# USB_HUB_3_0.net
KiCad netlist of a schematic drawn in Altium Designer
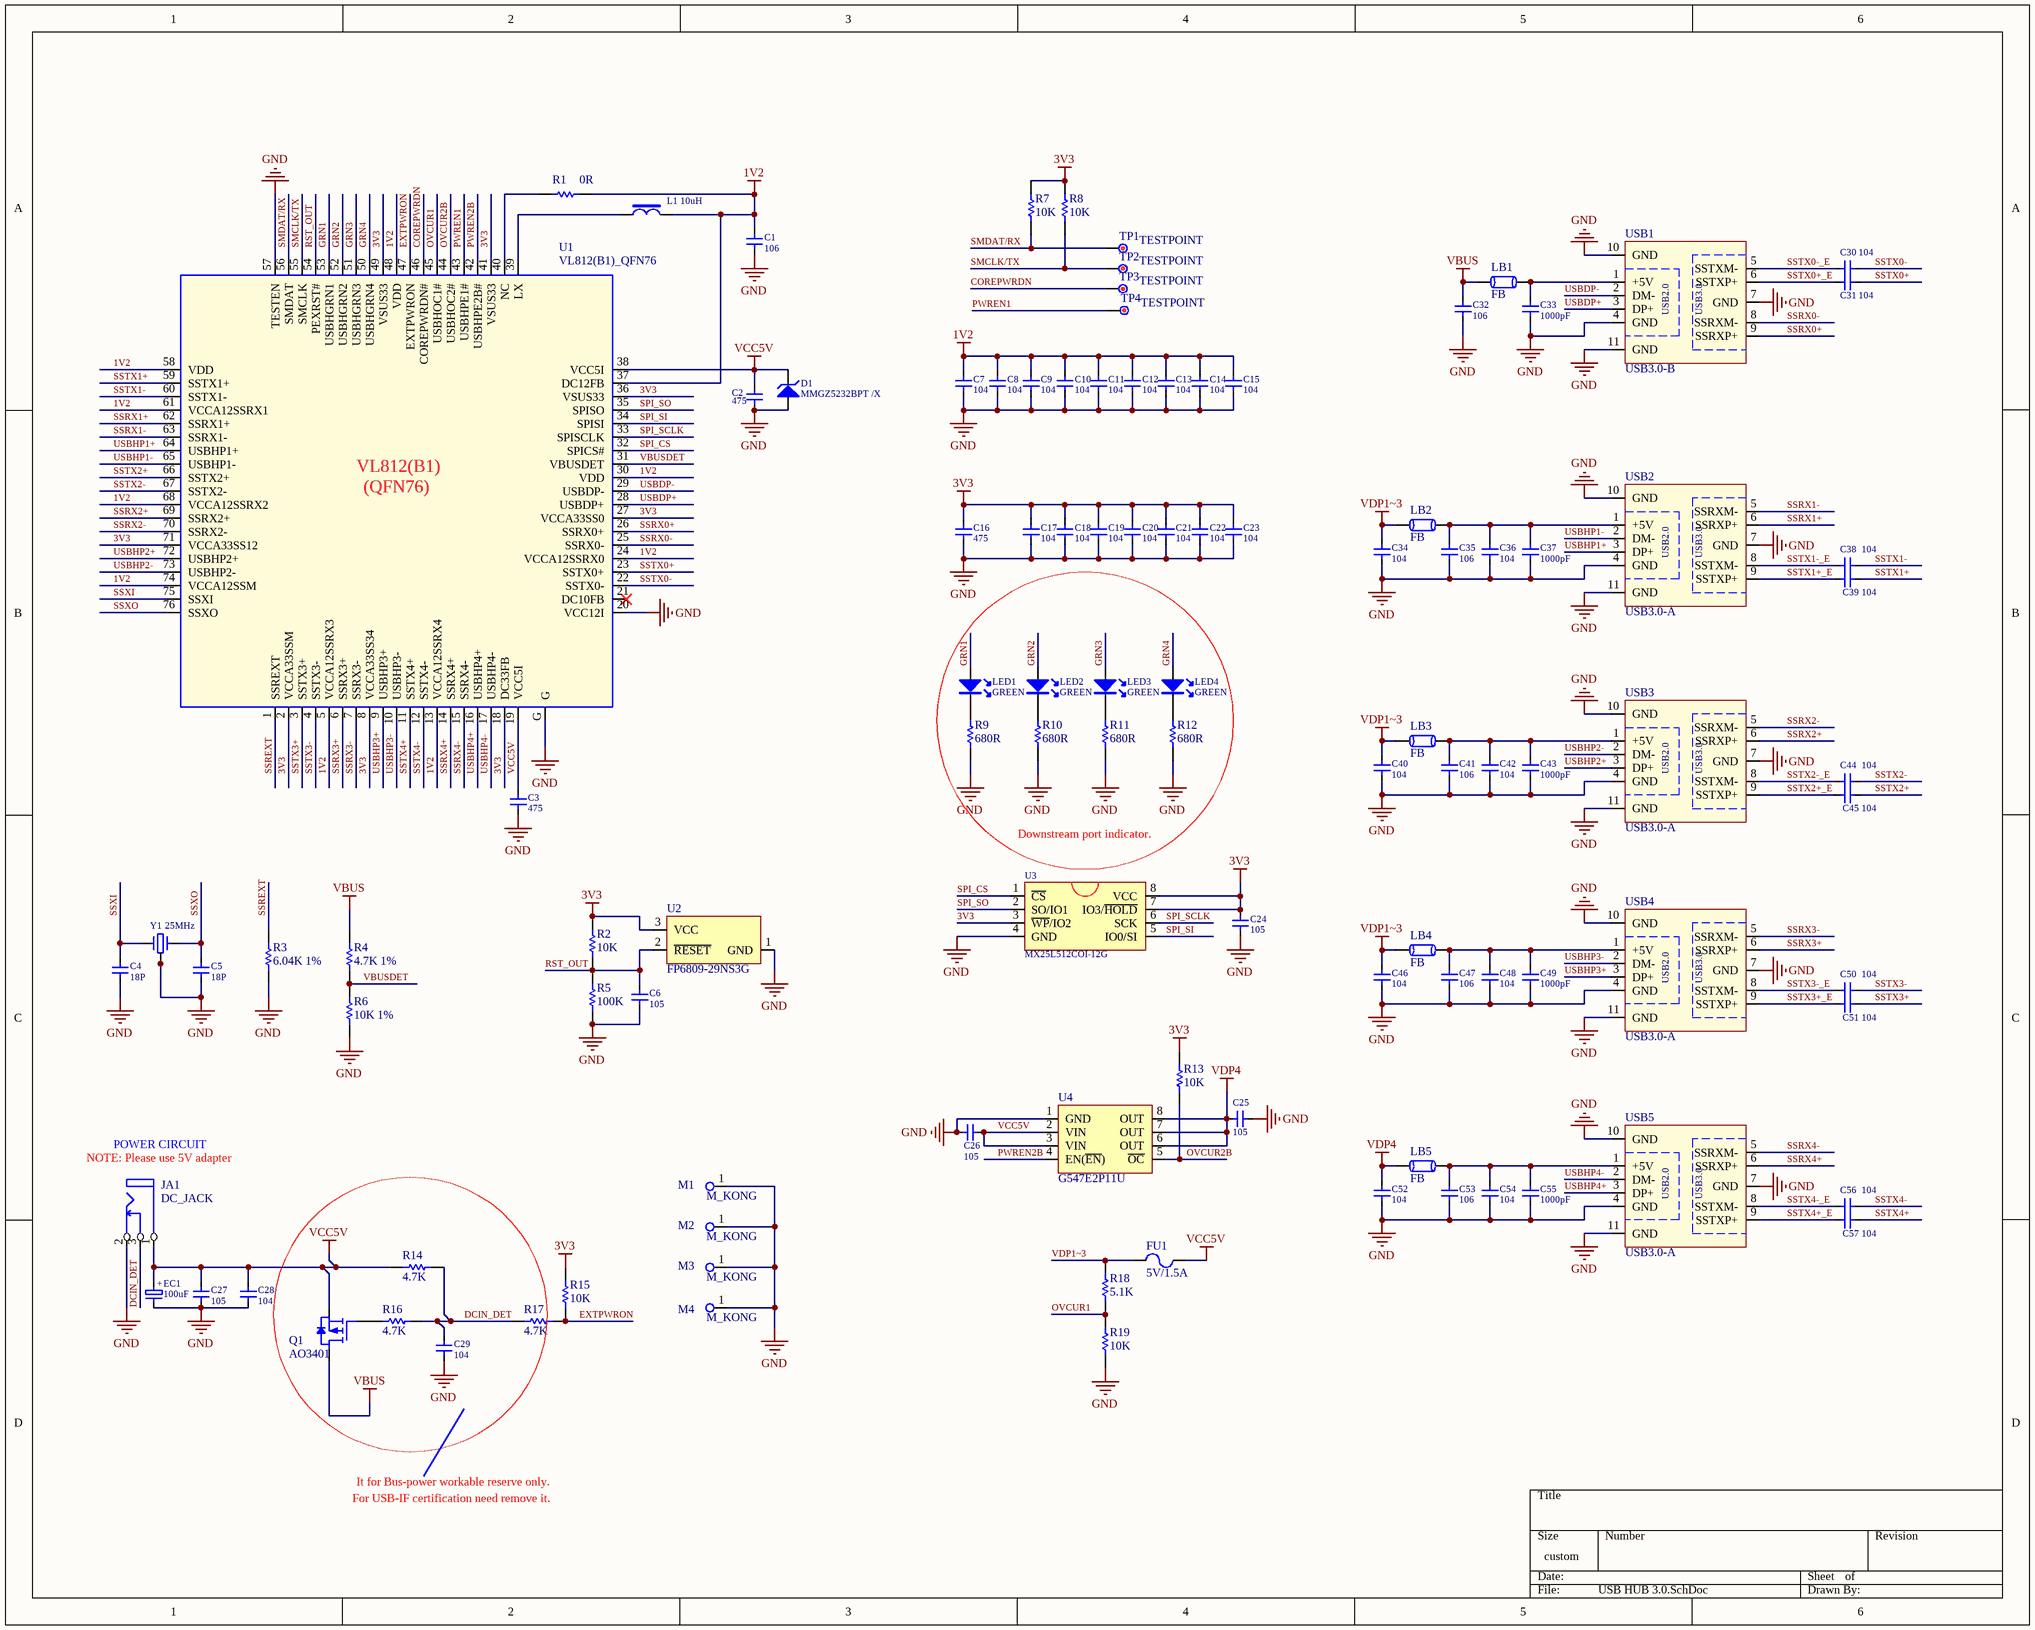
[diagram p0: USB HUB 3.0.SchDoc]

(export (version "E")
  (design (tool "Eeschema 10.0.6"))
  (components
    (comp (ref "C1")
      (value "106")
      (footprint "C0603")
      (description "Capacitor")
      (libsource (lib "lflj_com") (part "CAP"))
    )
    (comp (ref "C2")
      (value "475")
      (footprint "C0805")
      (description "Capacitor")
      (libsource (lib "lflj_com") (part "CAP"))
    )
    (comp (ref "C3")
      (value "475")
      (footprint "C0805")
      (description "Capacitor")
      (libsource (lib "lflj_com") (part "CAP"))
    )
    (comp (ref "C4")
      (value "18P")
      (footprint "C0402")
      (description "Capacitor")
      (libsource (lib "lflj_com") (part "CAP"))
    )
    (comp (ref "C5")
      (value "18P")
      (footprint "C0402")
      (description "Capacitor")
      (libsource (lib "lflj_com") (part "CAP"))
    )
    (comp (ref "C6")
      (value "105")
      (footprint "C0402")
      (description "Capacitor")
      (libsource (lib "lflj_com") (part "CAP"))
    )
    (comp (ref "C7")
      (value "104")
      (footprint "C0402")
      (description "Capacitor")
      (libsource (lib "lflj_com") (part "CAP"))
    )
    (comp (ref "C8")
      (value "104")
      (footprint "C0402")
      (description "Capacitor")
      (libsource (lib "lflj_com") (part "CAP"))
    )
    (comp (ref "C9")
      (value "104")
      (footprint "C0402")
      (description "Capacitor")
      (libsource (lib "lflj_com") (part "CAP"))
    )
    (comp (ref "C10")
      (value "104")
      (footprint "C0402")
      (description "Capacitor")
      (libsource (lib "lflj_com") (part "CAP"))
    )
    (comp (ref "C11")
      (value "104")
      (footprint "C0402")
      (description "Capacitor")
      (libsource (lib "lflj_com") (part "CAP"))
    )
    (comp (ref "C12")
      (value "104")
      (footprint "C0402")
      (description "Capacitor")
      (libsource (lib "lflj_com") (part "CAP"))
    )
    (comp (ref "C13")
      (value "104")
      (footprint "C0402")
      (description "Capacitor")
      (libsource (lib "lflj_com") (part "CAP"))
    )
    (comp (ref "C14")
      (value "104")
      (footprint "C0402")
      (description "Capacitor")
      (libsource (lib "lflj_com") (part "CAP"))
    )
    (comp (ref "C15")
      (value "104")
      (footprint "C0402")
      (description "Capacitor")
      (libsource (lib "lflj_com") (part "CAP"))
    )
    (comp (ref "C16")
      (value "475")
      (footprint "C0603")
      (description "Capacitor")
      (libsource (lib "lflj_com") (part "CAP"))
    )
    (comp (ref "C17")
      (value "104")
      (footprint "C0402")
      (description "Capacitor")
      (libsource (lib "lflj_com") (part "CAP"))
    )
    (comp (ref "C18")
      (value "104")
      (footprint "C0402")
      (description "Capacitor")
      (libsource (lib "lflj_com") (part "CAP"))
    )
    (comp (ref "C19")
      (value "104")
      (footprint "C0402")
      (description "Capacitor")
      (libsource (lib "lflj_com") (part "CAP"))
    )
    (comp (ref "C20")
      (value "104")
      (footprint "C0402")
      (description "Capacitor")
      (libsource (lib "lflj_com") (part "CAP"))
    )
    (comp (ref "C21")
      (value "104")
      (footprint "C0402")
      (description "Capacitor")
      (libsource (lib "lflj_com") (part "CAP"))
    )
    (comp (ref "C22")
      (value "104")
      (footprint "C0402")
      (description "Capacitor")
      (libsource (lib "lflj_com") (part "CAP"))
    )
    (comp (ref "C23")
      (value "104")
      (footprint "C0402")
      (description "Capacitor")
      (libsource (lib "lflj_com") (part "CAP"))
    )
    (comp (ref "C24")
      (value "105")
      (footprint "C0402")
      (description "Capacitor")
      (libsource (lib "lflj_com") (part "CAP"))
    )
    (comp (ref "C25")
      (value "105")
      (footprint "C0402")
      (description "Capacitor")
      (libsource (lib "lflj_com") (part "CAP"))
    )
    (comp (ref "C26")
      (value "105")
      (footprint "C0402")
      (description "Capacitor")
      (libsource (lib "lflj_com") (part "CAP"))
    )
    (comp (ref "C27")
      (value "105")
      (footprint "C0603")
      (description "Capacitor")
      (libsource (lib "lflj_com") (part "CAP"))
    )
    (comp (ref "C28")
      (value "104")
      (footprint "C0402")
      (description "Capacitor")
      (libsource (lib "lflj_com") (part "CAP"))
    )
    (comp (ref "C29")
      (value "104")
      (footprint "C0402")
      (description "Capacitor")
      (libsource (lib "lflj_com") (part "CAP"))
    )
    (comp (ref "C30")
      (value "104")
      (footprint "C0402")
      (description "Capacitor")
      (libsource (lib "lflj_com") (part "CAP"))
    )
    (comp (ref "C31")
      (value "104")
      (footprint "C0402")
      (description "Capacitor")
      (libsource (lib "lflj_com") (part "CAP"))
    )
    (comp (ref "C32")
      (value "106")
      (footprint "C0805")
      (description "Capacitor")
      (libsource (lib "lflj_com") (part "CAP"))
    )
    (comp (ref "C33")
      (value "1000pF")
      (footprint "C0402")
      (description "Capacitor")
      (libsource (lib "lflj_com") (part "CAP"))
    )
    (comp (ref "C34")
      (value "104")
      (footprint "C0402")
      (description "Capacitor")
      (libsource (lib "lflj_com") (part "CAP"))
    )
    (comp (ref "C35")
      (value "106")
      (footprint "C0805")
      (description "Capacitor")
      (libsource (lib "lflj_com") (part "CAP"))
    )
    (comp (ref "C36")
      (value "104")
      (footprint "C0402")
      (description "Capacitor")
      (libsource (lib "lflj_com") (part "CAP"))
    )
    (comp (ref "C37")
      (value "1000pF")
      (footprint "C0402")
      (description "Capacitor")
      (libsource (lib "lflj_com") (part "CAP"))
    )
    (comp (ref "C38")
      (value "104")
      (footprint "C0402")
      (description "Capacitor")
      (libsource (lib "lflj_com") (part "CAP"))
    )
    (comp (ref "C39")
      (value "104")
      (footprint "C0402")
      (description "Capacitor")
      (libsource (lib "lflj_com") (part "CAP"))
    )
    (comp (ref "C40")
      (value "104")
      (footprint "C0402")
      (description "Capacitor")
      (libsource (lib "lflj_com") (part "CAP"))
    )
    (comp (ref "C41")
      (value "106")
      (footprint "C0805")
      (description "Capacitor")
      (libsource (lib "lflj_com") (part "CAP"))
    )
    (comp (ref "C42")
      (value "104")
      (footprint "C0402")
      (description "Capacitor")
      (libsource (lib "lflj_com") (part "CAP"))
    )
    (comp (ref "C43")
      (value "1000pF")
      (footprint "C0402")
      (description "Capacitor")
      (libsource (lib "lflj_com") (part "CAP"))
    )
    (comp (ref "C44")
      (value "104")
      (footprint "C0402")
      (description "Capacitor")
      (libsource (lib "lflj_com") (part "CAP"))
    )
    (comp (ref "C45")
      (value "104")
      (footprint "C0402")
      (description "Capacitor")
      (libsource (lib "lflj_com") (part "CAP"))
    )
    (comp (ref "C46")
      (value "104")
      (footprint "C0402")
      (description "Capacitor")
      (libsource (lib "lflj_com") (part "CAP"))
    )
    (comp (ref "C47")
      (value "106")
      (footprint "C0805")
      (description "Capacitor")
      (libsource (lib "lflj_com") (part "CAP"))
    )
    (comp (ref "C48")
      (value "104")
      (footprint "C0402")
      (description "Capacitor")
      (libsource (lib "lflj_com") (part "CAP"))
    )
    (comp (ref "C49")
      (value "1000pF")
      (footprint "C0402")
      (description "Capacitor")
      (libsource (lib "lflj_com") (part "CAP"))
    )
    (comp (ref "C50")
      (value "104")
      (footprint "C0402")
      (description "Capacitor")
      (libsource (lib "lflj_com") (part "CAP"))
    )
    (comp (ref "C51")
      (value "104")
      (footprint "C0402")
      (description "Capacitor")
      (libsource (lib "lflj_com") (part "CAP"))
    )
    (comp (ref "C52")
      (value "104")
      (footprint "C0402")
      (description "Capacitor")
      (libsource (lib "lflj_com") (part "CAP"))
    )
    (comp (ref "C53")
      (value "106")
      (footprint "C0805")
      (description "Capacitor")
      (libsource (lib "lflj_com") (part "CAP"))
    )
    (comp (ref "C54")
      (value "104")
      (footprint "C0402")
      (description "Capacitor")
      (libsource (lib "lflj_com") (part "CAP"))
    )
    (comp (ref "C55")
      (value "1000pF")
      (footprint "C0402")
      (description "Capacitor")
      (libsource (lib "lflj_com") (part "CAP"))
    )
    (comp (ref "C56")
      (value "104")
      (footprint "C0402")
      (description "Capacitor")
      (libsource (lib "lflj_com") (part "CAP"))
    )
    (comp (ref "C57")
      (value "104")
      (footprint "C0402")
      (description "Capacitor")
      (libsource (lib "lflj_com") (part "CAP"))
    )
    (comp (ref "D1")
      (value "MMGZ5232BPT /X")
      (footprint "LL-34")
      (description "稳压二极管")
      (libsource (lib "lflj_com") (part "DIODE_Zener"))
    )
    (comp (ref "EC1")
      (value "100uF")
      (footprint "C_SMD(6.3x7.7)")
      (description "Electrolytic Capacitor")
      (libsource (lib "lflj_com") (part "ELECTRO"))
    )
    (comp (ref "FU1")
      (value "5V/1.5A")
      (footprint "FU1210")
      (description "保险丝")
      (libsource (lib "lflj_com") (part "FUSE"))
    )
    (comp (ref "JA1")
      (value "DC_JACK")
      (footprint "DC_005")
      (description "5V/9V电源座")
      (libsource (lib "lflj_com") (part "DC_JACK"))
    )
    (comp (ref "L1")
      (value "10uH")
      (footprint "CD53")
      (description "磁芯/铁心电感")
      (libsource (lib "lflj_com") (part "INDUCTOR1"))
    )
    (comp (ref "LB1")
      (value "FB")
      (footprint "L0805")
      (description "磁珠")
      (libsource (lib "lflj_com") (part "FB"))
    )
    (comp (ref "LB2")
      (value "FB")
      (footprint "L0805")
      (description "磁珠")
      (libsource (lib "lflj_com") (part "FB"))
    )
    (comp (ref "LB3")
      (value "FB")
      (footprint "L0805")
      (description "磁珠")
      (libsource (lib "lflj_com") (part "FB"))
    )
    (comp (ref "LB4")
      (value "FB")
      (footprint "L0805")
      (description "磁珠")
      (libsource (lib "lflj_com") (part "FB"))
    )
    (comp (ref "LB5")
      (value "FB")
      (footprint "L0805")
      (description "磁珠")
      (libsource (lib "lflj_com") (part "FB"))
    )
    (comp (ref "LED1")
      (value "GREEN")
      (footprint "LED_0603")
      (description "发光二极管")
      (libsource (lib "lflj_com") (part "LED"))
    )
    (comp (ref "LED2")
      (value "GREEN")
      (footprint "LED_0603")
      (description "发光二极管")
      (libsource (lib "lflj_com") (part "LED"))
    )
    (comp (ref "LED3")
      (value "GREEN")
      (footprint "LED_0603")
      (description "发光二极管")
      (libsource (lib "lflj_com") (part "LED"))
    )
    (comp (ref "LED4")
      (value "GREEN")
      (footprint "LED_0603")
      (description "发光二极管")
      (libsource (lib "lflj_com") (part "LED"))
    )
    (comp (ref "M1") (value "M_KONG") (footprint "M3*8") (libsource (lib "lflj_com") (part "M_KONG")))
    (comp (ref "M2") (value "M_KONG") (footprint "M3*8") (libsource (lib "lflj_com") (part "M_KONG")))
    (comp (ref "M3") (value "M_KONG") (footprint "M3*8") (libsource (lib "lflj_com") (part "M_KONG")))
    (comp (ref "M4") (value "M_KONG") (footprint "M3*8") (libsource (lib "lflj_com") (part "M_KONG")))
    (comp (ref "Q1")
      (value "AO3401")
      (footprint "SOT23")
      (description "P-Channel MOSFET")
      (libsource (lib "lflj_com") (part "MOSFET-P"))
    )
    (comp (ref "R1")
      (value "0R")
      (footprint "R0402")
      (description "电阻")
      (libsource (lib "lflj_com") (part "RES"))
    )
    (comp (ref "R2")
      (value "10K")
      (footprint "R0402")
      (description "电阻")
      (libsource (lib "lflj_com") (part "RES"))
    )
    (comp (ref "R3")
      (value "6.04K 1%")
      (footprint "R0402")
      (description "电阻")
      (libsource (lib "lflj_com") (part "RES"))
    )
    (comp (ref "R4")
      (value "4.7K 1%")
      (footprint "R0402")
      (description "电阻")
      (libsource (lib "lflj_com") (part "RES"))
    )
    (comp (ref "R5")
      (value "100K")
      (footprint "R0402")
      (description "电阻")
      (libsource (lib "lflj_com") (part "RES"))
    )
    (comp (ref "R6")
      (value "10K 1%")
      (footprint "R0402")
      (description "电阻")
      (libsource (lib "lflj_com") (part "RES"))
    )
    (comp (ref "R7")
      (value "10K")
      (footprint "R0402")
      (description "电阻")
      (libsource (lib "lflj_com") (part "RES"))
    )
    (comp (ref "R8")
      (value "10K")
      (footprint "R0402")
      (description "电阻")
      (libsource (lib "lflj_com") (part "RES"))
    )
    (comp (ref "R9")
      (value "680R")
      (footprint "R0402")
      (description "电阻")
      (libsource (lib "lflj_com") (part "RES"))
    )
    (comp (ref "R10")
      (value "680R")
      (footprint "R0402")
      (description "电阻")
      (libsource (lib "lflj_com") (part "RES"))
    )
    (comp (ref "R11")
      (value "680R")
      (footprint "R0402")
      (description "电阻")
      (libsource (lib "lflj_com") (part "RES"))
    )
    (comp (ref "R12")
      (value "680R")
      (footprint "R0402")
      (description "电阻")
      (libsource (lib "lflj_com") (part "RES"))
    )
    (comp (ref "R13")
      (value "10K")
      (footprint "R0402")
      (description "电阻")
      (libsource (lib "lflj_com") (part "RES"))
    )
    (comp (ref "R14")
      (value "4.7K")
      (footprint "R0402")
      (description "电阻")
      (libsource (lib "lflj_com") (part "RES"))
    )
    (comp (ref "R15")
      (value "10K")
      (footprint "R0402")
      (description "电阻")
      (libsource (lib "lflj_com") (part "RES"))
    )
    (comp (ref "R16")
      (value "4.7K")
      (footprint "R0402")
      (description "电阻")
      (libsource (lib "lflj_com") (part "RES"))
    )
    (comp (ref "R17")
      (value "4.7K")
      (footprint "R0402")
      (description "电阻")
      (libsource (lib "lflj_com") (part "RES"))
    )
    (comp (ref "R18")
      (value "5.1K")
      (footprint "R0402")
      (description "电阻")
      (libsource (lib "lflj_com") (part "RES"))
    )
    (comp (ref "R19")
      (value "10K")
      (footprint "R0402")
      (description "电阻")
      (libsource (lib "lflj_com") (part "RES"))
    )
    (comp (ref "TP1")
      (value "TESTPOINT")
      (footprint "TP")
      (description "测试点")
      (libsource (lib "lflj_com") (part "TP"))
    )
    (comp (ref "TP2")
      (value "TESTPOINT")
      (footprint "TP")
      (description "测试点")
      (libsource (lib "lflj_com") (part "TP"))
    )
    (comp (ref "TP3")
      (value "TESTPOINT")
      (footprint "TP")
      (description "测试点")
      (libsource (lib "lflj_com") (part "TP"))
    )
    (comp (ref "TP4")
      (value "TESTPOINT")
      (footprint "TP")
      (description "测试点")
      (libsource (lib "lflj_com") (part "TP"))
    )
    (comp (ref "U1")
      (value "VL812(B1)_QFN76")
      (footprint "QFN76-0.4_9*9")
      (description "USB 3.0 HUB Controller")
      (libsource (lib "lflj_IC") (part "VL812(B1)_099"))
    )
    (comp (ref "U2")
      (value "FP6809-29NS3G")
      (footprint "SOT23")
      (description "微处理器复位芯片")
      (libsource (lib "lflj_IC") (part "FP6809"))
    )
    (comp (ref "U3")
      (value "MX25L512COI-12G")
      (footprint "SOIC8")
      (description "Flash")
      (libsource (lib "lflj_IC") (part "A25QXX"))
    )
    (comp (ref "U4")
      (value "G547E2P11U")
      (footprint "SOP8")
      (description "MOS管开关芯片")
      (libsource (lib "lflj_IC") (part "G547E2P11U"))
    )
    (comp (ref "USB1")
      (value "USB3.0-B")
      (footprint "USB3.0-B")
      (libsource (lib "lflj_com") (part "USB3.0-B"))
    )
    (comp (ref "USB2")
      (value "USB3.0-A")
      (footprint "USB3.0-A")
      (libsource (lib "lflj_com") (part "USB3.0-A"))
    )
    (comp (ref "USB3")
      (value "USB3.0-A")
      (footprint "USB3.0-A")
      (libsource (lib "lflj_com") (part "USB3.0-A"))
    )
    (comp (ref "USB4")
      (value "USB3.0-A")
      (footprint "USB3.0-A")
      (libsource (lib "lflj_com") (part "USB3.0-A"))
    )
    (comp (ref "USB5")
      (value "USB3.0-A")
      (footprint "USB3.0-A")
      (libsource (lib "lflj_com") (part "USB3.0-A"))
    )
    (comp (ref "Y1")
      (value "25MHz")
      (footprint "0SC-3225_4")
      (description "晶振")
      (libsource (lib "lflj_com") (part "CRYSTAL_4PIN"))
    )
  )
  (nets
    (net (code "1") (name "/COREPWRDN") (class "Default")
      (node (ref "TP3") (pin "1") (pinfunction "1_1") (pintype "passive"))
      (node (ref "U1") (pin "46") (pinfunction "COREPWRDN#_46") (pintype "passive"))
    )
    (net (code "2") (name "/DCIN_DET") (class "Default")
      (node (ref "C29") (pin "2") (pinfunction "2_2") (pintype "passive"))
      (node (ref "JA1") (pin "3") (pinfunction "3_3") (pintype "passive"))
      (node (ref "R14") (pin "2") (pinfunction "2_2") (pintype "passive"))
      (node (ref "R16") (pin "1") (pinfunction "1_1") (pintype "passive"))
      (node (ref "R17") (pin "2") (pinfunction "2_2") (pintype "passive"))
    )
    (net (code "3") (name "/EXTPWRON") (class "Default")
      (node (ref "R15") (pin "1") (pinfunction "1_1") (pintype "passive"))
      (node (ref "R17") (pin "1") (pinfunction "1_1") (pintype "passive"))
      (node (ref "U1") (pin "47") (pinfunction "EXTPWRON_47") (pintype "passive"))
    )
    (net (code "4") (name "/GRN1") (class "Default")
      (node (ref "LED1") (pin "1") (pinfunction "A_1") (pintype "passive"))
      (node (ref "U1") (pin "53") (pinfunction "USBHGRN1_53") (pintype "passive"))
    )
    (net (code "5") (name "/GRN2") (class "Default")
      (node (ref "LED2") (pin "1") (pinfunction "A_1") (pintype "passive"))
      (node (ref "U1") (pin "52") (pinfunction "USBHGRN2_52") (pintype "passive"))
    )
    (net (code "6") (name "/GRN3") (class "Default")
      (node (ref "LED3") (pin "1") (pinfunction "A_1") (pintype "passive"))
      (node (ref "U1") (pin "51") (pinfunction "USBHGRN3_51") (pintype "passive"))
    )
    (net (code "7") (name "/GRN4") (class "Default")
      (node (ref "LED4") (pin "1") (pinfunction "A_1") (pintype "passive"))
      (node (ref "U1") (pin "50") (pinfunction "USBHGRN4_50") (pintype "passive"))
    )
    (net (code "8") (name "/OVCUR1") (class "Default")
      (node (ref "R18") (pin "2") (pinfunction "2_2") (pintype "passive"))
      (node (ref "R19") (pin "1") (pinfunction "1_1") (pintype "passive"))
      (node (ref "U1") (pin "45") (pinfunction "USBHOC1#_45") (pintype "passive"))
    )
    (net (code "9") (name "/OVCUR2B") (class "Default")
      (node (ref "R13") (pin "1") (pinfunction "1_1") (pintype "passive"))
      (node (ref "U1") (pin "44") (pinfunction "USBHOC2#_44") (pintype "passive"))
      (node (ref "U4") (pin "5") (pinfunction "~{OC}_5") (pintype "passive"))
    )
    (net (code "10") (name "/PWREN1") (class "Default")
      (node (ref "TP4") (pin "1") (pinfunction "1_1") (pintype "passive"))
      (node (ref "U1") (pin "43") (pinfunction "USBHPE1#_43") (pintype "passive"))
    )
    (net (code "11") (name "/PWREN2B") (class "Default")
      (node (ref "U1") (pin "42") (pinfunction "USBHPE2B#_42") (pintype "passive"))
      (node (ref "U4") (pin "4") (pinfunction "EN(~{EN})_4") (pintype "passive"))
    )
    (net (code "12") (name "/RST_OUT") (class "Default")
      (node (ref "C6") (pin "1") (pinfunction "1_1") (pintype "passive"))
      (node (ref "R2") (pin "2") (pinfunction "2_2") (pintype "passive"))
      (node (ref "R5") (pin "1") (pinfunction "1_1") (pintype "passive"))
      (node (ref "U1") (pin "54") (pinfunction "PEXRST#_54") (pintype "passive"))
      (node (ref "U2") (pin "2") (pinfunction "~{RESET}_2") (pintype "passive"))
    )
    (net (code "13") (name "/SMCLK{slash}TX") (class "Default")
      (node (ref "R8") (pin "2") (pinfunction "2_2") (pintype "passive"))
      (node (ref "TP2") (pin "1") (pinfunction "1_1") (pintype "passive"))
      (node (ref "U1") (pin "55") (pinfunction "SMCLK_55") (pintype "passive"))
    )
    (net (code "14") (name "/SMDAT{slash}RX") (class "Default")
      (node (ref "R7") (pin "2") (pinfunction "2_2") (pintype "passive"))
      (node (ref "TP1") (pin "1") (pinfunction "1_1") (pintype "passive"))
      (node (ref "U1") (pin "56") (pinfunction "SMDAT_56") (pintype "passive"))
    )
    (net (code "15") (name "/SPI_CS") (class "Default")
      (node (ref "U1") (pin "32") (pinfunction "SPICS#_32") (pintype "passive"))
      (node (ref "U3") (pin "1") (pinfunction "~{CS}_1") (pintype "passive"))
    )
    (net (code "16") (name "/SPI_SCLK") (class "Default")
      (node (ref "U1") (pin "33") (pinfunction "SPISCLK_33") (pintype "passive"))
      (node (ref "U3") (pin "6") (pinfunction "SCK_6") (pintype "passive"))
    )
    (net (code "17") (name "/SPI_SI") (class "Default")
      (node (ref "U1") (pin "34") (pinfunction "SPISI_34") (pintype "passive"))
      (node (ref "U3") (pin "5") (pinfunction "IO0/SI_5") (pintype "passive"))
    )
    (net (code "18") (name "/SPI_SO") (class "Default")
      (node (ref "U1") (pin "35") (pinfunction "SPISO_35") (pintype "passive"))
      (node (ref "U3") (pin "2") (pinfunction "SO/IO1_2") (pintype "passive"))
    )
    (net (code "19") (name "/SSREXT") (class "Default")
      (node (ref "R3") (pin "1") (pinfunction "1_1") (pintype "passive"))
      (node (ref "U1") (pin "1") (pinfunction "SSREXT_1") (pintype "passive"))
    )
    (net (code "20") (name "/SSRX0+") (class "Default")
      (node (ref "U1") (pin "26") (pinfunction "SSRX0+_26") (pintype "passive"))
      (node (ref "USB1") (pin "9") (pinfunction "SSRXP+_9") (pintype "passive"))
    )
    (net (code "21") (name "/SSRX0-") (class "Default")
      (node (ref "U1") (pin "25") (pinfunction "SSRX0-_25") (pintype "passive"))
      (node (ref "USB1") (pin "8") (pinfunction "SSRXM-_8") (pintype "passive"))
    )
    (net (code "22") (name "/SSRX1+") (class "Default")
      (node (ref "U1") (pin "62") (pinfunction "SSRX1+_62") (pintype "passive"))
      (node (ref "USB2") (pin "6") (pinfunction "SSRXP+_6") (pintype "passive"))
    )
    (net (code "23") (name "/SSRX1-") (class "Default")
      (node (ref "U1") (pin "63") (pinfunction "SSRX1-_63") (pintype "power_in"))
      (node (ref "USB2") (pin "5") (pinfunction "SSRXM-_5") (pintype "passive"))
    )
    (net (code "24") (name "/SSRX2+") (class "Default")
      (node (ref "U1") (pin "69") (pinfunction "SSRX2+_69") (pintype "passive"))
      (node (ref "USB3") (pin "6") (pinfunction "SSRXP+_6") (pintype "passive"))
    )
    (net (code "25") (name "/SSRX2-") (class "Default")
      (node (ref "U1") (pin "70") (pinfunction "SSRX2-_70") (pintype "passive"))
      (node (ref "USB3") (pin "5") (pinfunction "SSRXM-_5") (pintype "passive"))
    )
    (net (code "26") (name "/SSRX3+") (class "Default")
      (node (ref "U1") (pin "6") (pinfunction "SSRX3+_6") (pintype "passive"))
      (node (ref "USB4") (pin "6") (pinfunction "SSRXP+_6") (pintype "passive"))
    )
    (net (code "27") (name "/SSRX3-") (class "Default")
      (node (ref "U1") (pin "7") (pinfunction "SSRX3-_7") (pintype "passive"))
      (node (ref "USB4") (pin "5") (pinfunction "SSRXM-_5") (pintype "passive"))
    )
    (net (code "28") (name "/SSRX4+") (class "Default")
      (node (ref "U1") (pin "14") (pinfunction "SSRX4+_14") (pintype "passive"))
      (node (ref "USB5") (pin "6") (pinfunction "SSRXP+_6") (pintype "passive"))
    )
    (net (code "29") (name "/SSRX4-") (class "Default")
      (node (ref "U1") (pin "15") (pinfunction "SSRX4-_15") (pintype "passive"))
      (node (ref "USB5") (pin "5") (pinfunction "SSRXM-_5") (pintype "passive"))
    )
    (net (code "30") (name "/SSTX0+") (class "Default")
      (node (ref "C31") (pin "2") (pinfunction "2_2") (pintype "passive"))
      (node (ref "U1") (pin "23") (pinfunction "SSTX0+_23") (pintype "passive"))
    )
    (net (code "31") (name "/SSTX0+_E") (class "Default")
      (node (ref "C31") (pin "1") (pinfunction "1_1") (pintype "passive"))
      (node (ref "USB1") (pin "6") (pinfunction "SSTXP+_6") (pintype "passive"))
    )
    (net (code "32") (name "/SSTX0-") (class "Default")
      (node (ref "C30") (pin "2") (pinfunction "2_2") (pintype "passive"))
      (node (ref "U1") (pin "22") (pinfunction "SSTX0-_22") (pintype "passive"))
    )
    (net (code "33") (name "/SSTX0-_E") (class "Default")
      (node (ref "C30") (pin "1") (pinfunction "1_1") (pintype "passive"))
      (node (ref "USB1") (pin "5") (pinfunction "SSTXM-_5") (pintype "passive"))
    )
    (net (code "34") (name "/SSTX1+") (class "Default")
      (node (ref "C39") (pin "2") (pinfunction "2_2") (pintype "passive"))
      (node (ref "U1") (pin "59") (pinfunction "SSTX1+_59") (pintype "passive"))
    )
    (net (code "35") (name "/SSTX1+_E") (class "Default")
      (node (ref "C39") (pin "1") (pinfunction "1_1") (pintype "passive"))
      (node (ref "USB2") (pin "9") (pinfunction "SSTXP+_9") (pintype "passive"))
    )
    (net (code "36") (name "/SSTX1-") (class "Default")
      (node (ref "C38") (pin "2") (pinfunction "2_2") (pintype "passive"))
      (node (ref "U1") (pin "60") (pinfunction "SSTX1-_60") (pintype "passive"))
    )
    (net (code "37") (name "/SSTX1-_E") (class "Default")
      (node (ref "C38") (pin "1") (pinfunction "1_1") (pintype "passive"))
      (node (ref "USB2") (pin "8") (pinfunction "SSTXM-_8") (pintype "passive"))
    )
    (net (code "38") (name "/SSTX2+") (class "Default")
      (node (ref "C45") (pin "2") (pinfunction "2_2") (pintype "passive"))
      (node (ref "U1") (pin "66") (pinfunction "SSTX2+_66") (pintype "passive"))
    )
    (net (code "39") (name "/SSTX2+_E") (class "Default")
      (node (ref "C45") (pin "1") (pinfunction "1_1") (pintype "passive"))
      (node (ref "USB3") (pin "9") (pinfunction "SSTXP+_9") (pintype "passive"))
    )
    (net (code "40") (name "/SSTX2-") (class "Default")
      (node (ref "C44") (pin "2") (pinfunction "2_2") (pintype "passive"))
      (node (ref "U1") (pin "67") (pinfunction "SSTX2-_67") (pintype "passive"))
    )
    (net (code "41") (name "/SSTX2-_E") (class "Default")
      (node (ref "C44") (pin "1") (pinfunction "1_1") (pintype "passive"))
      (node (ref "USB3") (pin "8") (pinfunction "SSTXM-_8") (pintype "passive"))
    )
    (net (code "42") (name "/SSTX3+") (class "Default")
      (node (ref "C51") (pin "2") (pinfunction "2_2") (pintype "passive"))
      (node (ref "U1") (pin "3") (pinfunction "SSTX3+_3") (pintype "passive"))
    )
    (net (code "43") (name "/SSTX3+_E") (class "Default")
      (node (ref "C51") (pin "1") (pinfunction "1_1") (pintype "passive"))
      (node (ref "USB4") (pin "9") (pinfunction "SSTXP+_9") (pintype "passive"))
    )
    (net (code "44") (name "/SSTX3-") (class "Default")
      (node (ref "C50") (pin "2") (pinfunction "2_2") (pintype "passive"))
      (node (ref "U1") (pin "4") (pinfunction "SSTX3-_4") (pintype "passive"))
    )
    (net (code "45") (name "/SSTX3-_E") (class "Default")
      (node (ref "C50") (pin "1") (pinfunction "1_1") (pintype "passive"))
      (node (ref "USB4") (pin "8") (pinfunction "SSTXM-_8") (pintype "passive"))
    )
    (net (code "46") (name "/SSTX4+") (class "Default")
      (node (ref "C57") (pin "2") (pinfunction "2_2") (pintype "passive"))
      (node (ref "U1") (pin "11") (pinfunction "SSTX4+_11") (pintype "passive"))
    )
    (net (code "47") (name "/SSTX4+_E") (class "Default")
      (node (ref "C57") (pin "1") (pinfunction "1_1") (pintype "passive"))
      (node (ref "USB5") (pin "9") (pinfunction "SSTXP+_9") (pintype "passive"))
    )
    (net (code "48") (name "/SSTX4-") (class "Default")
      (node (ref "C56") (pin "2") (pinfunction "2_2") (pintype "passive"))
      (node (ref "U1") (pin "12") (pinfunction "SSTX4-_12") (pintype "passive"))
    )
    (net (code "49") (name "/SSTX4-_E") (class "Default")
      (node (ref "C56") (pin "1") (pinfunction "1_1") (pintype "passive"))
      (node (ref "USB5") (pin "8") (pinfunction "SSTXM-_8") (pintype "passive"))
    )
    (net (code "50") (name "/SSXI") (class "Default")
      (node (ref "C4") (pin "1") (pinfunction "1_1") (pintype "passive"))
      (node (ref "U1") (pin "75") (pinfunction "SSXI_75") (pintype "passive"))
      (node (ref "Y1") (pin "1") (pinfunction "1_1") (pintype "passive"))
    )
    (net (code "51") (name "/SSXO") (class "Default")
      (node (ref "C5") (pin "1") (pinfunction "1_1") (pintype "passive"))
      (node (ref "U1") (pin "76") (pinfunction "SSXO_76") (pintype "passive"))
      (node (ref "Y1") (pin "2") (pinfunction "2_2") (pintype "passive"))
    )
    (net (code "52") (name "/USBDP+") (class "Default")
      (node (ref "U1") (pin "28") (pinfunction "USBDP+_28") (pintype "passive"))
      (node (ref "USB1") (pin "3") (pinfunction "DP+_3") (pintype "passive"))
    )
    (net (code "53") (name "/USBDP-") (class "Default")
      (node (ref "U1") (pin "29") (pinfunction "USBDP-_29") (pintype "passive"))
      (node (ref "USB1") (pin "2") (pinfunction "DM-_2") (pintype "passive"))
    )
    (net (code "54") (name "/USBHP1+") (class "Default")
      (node (ref "U1") (pin "64") (pinfunction "USBHP1+_64") (pintype "passive"))
      (node (ref "USB2") (pin "3") (pinfunction "DP+_3") (pintype "passive"))
    )
    (net (code "55") (name "/USBHP1-") (class "Default")
      (node (ref "U1") (pin "65") (pinfunction "USBHP1-_65") (pintype "passive"))
      (node (ref "USB2") (pin "2") (pinfunction "DM-_2") (pintype "passive"))
    )
    (net (code "56") (name "/USBHP2+") (class "Default")
      (node (ref "U1") (pin "72") (pinfunction "USBHP2+_72") (pintype "passive"))
      (node (ref "USB3") (pin "3") (pinfunction "DP+_3") (pintype "passive"))
    )
    (net (code "57") (name "/USBHP2-") (class "Default")
      (node (ref "U1") (pin "73") (pinfunction "USBHP2-_73") (pintype "passive"))
      (node (ref "USB3") (pin "2") (pinfunction "DM-_2") (pintype "passive"))
    )
    (net (code "58") (name "/USBHP3+") (class "Default")
      (node (ref "U1") (pin "9") (pinfunction "USBHP3+_9") (pintype "passive"))
      (node (ref "USB4") (pin "3") (pinfunction "DP+_3") (pintype "passive"))
    )
    (net (code "59") (name "/USBHP3-") (class "Default")
      (node (ref "U1") (pin "10") (pinfunction "USBHP3-_10") (pintype "passive"))
      (node (ref "USB4") (pin "2") (pinfunction "DM-_2") (pintype "passive"))
    )
    (net (code "60") (name "/USBHP4+") (class "Default")
      (node (ref "U1") (pin "16") (pinfunction "USBHP4+_16") (pintype "passive"))
      (node (ref "USB5") (pin "3") (pinfunction "DP+_3") (pintype "passive"))
    )
    (net (code "61") (name "/USBHP4-") (class "Default")
      (node (ref "U1") (pin "17") (pinfunction "USBHP4-_17") (pintype "passive"))
      (node (ref "USB5") (pin "2") (pinfunction "DM-_2") (pintype "passive"))
    )
    (net (code "62") (name "/VBUSDET") (class "Default")
      (node (ref "R4") (pin "2") (pinfunction "2_2") (pintype "passive"))
      (node (ref "R6") (pin "1") (pinfunction "1_1") (pintype "passive"))
      (node (ref "U1") (pin "31") (pinfunction "VBUSDET_31") (pintype "power_in"))
    )
    (net (code "63") (name "1V2") (class "Default")
      (node (ref "C1") (pin "1") (pinfunction "1_1") (pintype "passive"))
      (node (ref "C10") (pin "1") (pinfunction "1_1") (pintype "passive"))
      (node (ref "C11") (pin "1") (pinfunction "1_1") (pintype "passive"))
      (node (ref "C12") (pin "1") (pinfunction "1_1") (pintype "passive"))
      (node (ref "C13") (pin "1") (pinfunction "1_1") (pintype "passive"))
      (node (ref "C14") (pin "1") (pinfunction "1_1") (pintype "passive"))
      (node (ref "C15") (pin "1") (pinfunction "1_1") (pintype "passive"))
      (node (ref "C7") (pin "1") (pinfunction "1_1") (pintype "passive"))
      (node (ref "C8") (pin "1") (pinfunction "1_1") (pintype "passive"))
      (node (ref "C9") (pin "1") (pinfunction "1_1") (pintype "passive"))
      (node (ref "L1") (pin "2") (pinfunction "2_2") (pintype "passive"))
      (node (ref "R1") (pin "1") (pinfunction "1_1") (pintype "passive"))
      (node (ref "U1") (pin "13") (pinfunction "VCCA12SSRX4_13") (pintype "power_in"))
      (node (ref "U1") (pin "24") (pinfunction "VCCA12SSRX0_24") (pintype "power_in"))
      (node (ref "U1") (pin "30") (pinfunction "VDD_30") (pintype "power_in"))
      (node (ref "U1") (pin "37") (pinfunction "DC12FB_37") (pintype "passive"))
      (node (ref "U1") (pin "48") (pinfunction "VDD_48") (pintype "power_in"))
      (node (ref "U1") (pin "5") (pinfunction "VCCA12SSRX3_5") (pintype "power_in"))
      (node (ref "U1") (pin "58") (pinfunction "VDD_58") (pintype "power_in"))
      (node (ref "U1") (pin "61") (pinfunction "VCCA12SSRX1_61") (pintype "power_in"))
      (node (ref "U1") (pin "68") (pinfunction "VCCA12SSRX2_68") (pintype "power_in"))
      (node (ref "U1") (pin "74") (pinfunction "VCCA12SSM_74") (pintype "power_in"))
    )
    (net (code "64") (name "3V3") (class "Default")
      (node (ref "C16") (pin "1") (pinfunction "1_1") (pintype "passive"))
      (node (ref "C17") (pin "1") (pinfunction "1_1") (pintype "passive"))
      (node (ref "C18") (pin "1") (pinfunction "1_1") (pintype "passive"))
      (node (ref "C19") (pin "1") (pinfunction "1_1") (pintype "passive"))
      (node (ref "C20") (pin "1") (pinfunction "1_1") (pintype "passive"))
      (node (ref "C21") (pin "1") (pinfunction "1_1") (pintype "passive"))
      (node (ref "C22") (pin "1") (pinfunction "1_1") (pintype "passive"))
      (node (ref "C23") (pin "1") (pinfunction "1_1") (pintype "passive"))
      (node (ref "C24") (pin "1") (pinfunction "1_1") (pintype "passive"))
      (node (ref "R13") (pin "2") (pinfunction "2_2") (pintype "passive"))
      (node (ref "R15") (pin "2") (pinfunction "2_2") (pintype "passive"))
      (node (ref "R2") (pin "1") (pinfunction "1_1") (pintype "passive"))
      (node (ref "R7") (pin "1") (pinfunction "1_1") (pintype "passive"))
      (node (ref "R8") (pin "1") (pinfunction "1_1") (pintype "passive"))
      (node (ref "U1") (pin "18") (pinfunction "DC33FB_18") (pintype "power_in"))
      (node (ref "U1") (pin "2") (pinfunction "VCCA33SSM_2") (pintype "power_in"))
      (node (ref "U1") (pin "27") (pinfunction "VCCA33SS0_27") (pintype "power_in"))
      (node (ref "U1") (pin "36") (pinfunction "VSUS33_36") (pintype "power_in"))
      (node (ref "U1") (pin "41") (pinfunction "VSUS33_41") (pintype "power_in"))
      (node (ref "U1") (pin "49") (pinfunction "VSUS33_49") (pintype "power_in"))
      (node (ref "U1") (pin "71") (pinfunction "VCCA33SS12_71") (pintype "power_in"))
      (node (ref "U1") (pin "8") (pinfunction "VCCA33SS34_8") (pintype "power_in"))
      (node (ref "U2") (pin "3") (pinfunction "VCC_3") (pintype "passive"))
      (node (ref "U3") (pin "3") (pinfunction "~{WP}/IO2_3") (pintype "passive"))
      (node (ref "U3") (pin "7") (pinfunction "IO3/~{HOLD}_7") (pintype "passive"))
      (node (ref "U3") (pin "8") (pinfunction "VCC_8") (pintype "passive"))
    )
    (net (code "65") (name "GND") (class "Default")
      (node (ref "C1") (pin "2") (pinfunction "2_2") (pintype "passive"))
      (node (ref "C10") (pin "2") (pinfunction "2_2") (pintype "passive"))
      (node (ref "C11") (pin "2") (pinfunction "2_2") (pintype "passive"))
      (node (ref "C12") (pin "2") (pinfunction "2_2") (pintype "passive"))
      (node (ref "C13") (pin "2") (pinfunction "2_2") (pintype "passive"))
      (node (ref "C14") (pin "2") (pinfunction "2_2") (pintype "passive"))
      (node (ref "C15") (pin "2") (pinfunction "2_2") (pintype "passive"))
      (node (ref "C16") (pin "2") (pinfunction "2_2") (pintype "passive"))
      (node (ref "C17") (pin "2") (pinfunction "2_2") (pintype "passive"))
      (node (ref "C18") (pin "2") (pinfunction "2_2") (pintype "passive"))
      (node (ref "C19") (pin "2") (pinfunction "2_2") (pintype "passive"))
      (node (ref "C2") (pin "2") (pinfunction "2_2") (pintype "passive"))
      (node (ref "C20") (pin "2") (pinfunction "2_2") (pintype "passive"))
      (node (ref "C21") (pin "2") (pinfunction "2_2") (pintype "passive"))
      (node (ref "C22") (pin "2") (pinfunction "2_2") (pintype "passive"))
      (node (ref "C23") (pin "2") (pinfunction "2_2") (pintype "passive"))
      (node (ref "C24") (pin "2") (pinfunction "2_2") (pintype "passive"))
      (node (ref "C25") (pin "2") (pinfunction "2_2") (pintype "passive"))
      (node (ref "C26") (pin "1") (pinfunction "1_1") (pintype "passive"))
      (node (ref "C27") (pin "1") (pinfunction "1_1") (pintype "passive"))
      (node (ref "C28") (pin "1") (pinfunction "1_1") (pintype "passive"))
      (node (ref "C29") (pin "1") (pinfunction "1_1") (pintype "passive"))
      (node (ref "C3") (pin "2") (pinfunction "2_2") (pintype "passive"))
      (node (ref "C32") (pin "2") (pinfunction "2_2") (pintype "passive"))
      (node (ref "C33") (pin "2") (pinfunction "2_2") (pintype "passive"))
      (node (ref "C34") (pin "2") (pinfunction "2_2") (pintype "passive"))
      (node (ref "C35") (pin "2") (pinfunction "2_2") (pintype "passive"))
      (node (ref "C36") (pin "2") (pinfunction "2_2") (pintype "passive"))
      (node (ref "C37") (pin "2") (pinfunction "2_2") (pintype "passive"))
      (node (ref "C4") (pin "2") (pinfunction "2_2") (pintype "passive"))
      (node (ref "C40") (pin "2") (pinfunction "2_2") (pintype "passive"))
      (node (ref "C41") (pin "2") (pinfunction "2_2") (pintype "passive"))
      (node (ref "C42") (pin "2") (pinfunction "2_2") (pintype "passive"))
      (node (ref "C43") (pin "2") (pinfunction "2_2") (pintype "passive"))
      (node (ref "C46") (pin "2") (pinfunction "2_2") (pintype "passive"))
      (node (ref "C47") (pin "2") (pinfunction "2_2") (pintype "passive"))
      (node (ref "C48") (pin "2") (pinfunction "2_2") (pintype "passive"))
      (node (ref "C49") (pin "2") (pinfunction "2_2") (pintype "passive"))
      (node (ref "C5") (pin "2") (pinfunction "2_2") (pintype "passive"))
      (node (ref "C52") (pin "2") (pinfunction "2_2") (pintype "passive"))
      (node (ref "C53") (pin "2") (pinfunction "2_2") (pintype "passive"))
      (node (ref "C54") (pin "2") (pinfunction "2_2") (pintype "passive"))
      (node (ref "C55") (pin "2") (pinfunction "2_2") (pintype "passive"))
      (node (ref "C6") (pin "2") (pinfunction "2_2") (pintype "passive"))
      (node (ref "C7") (pin "2") (pinfunction "2_2") (pintype "passive"))
      (node (ref "C8") (pin "2") (pinfunction "2_2") (pintype "passive"))
      (node (ref "C9") (pin "2") (pinfunction "2_2") (pintype "passive"))
      (node (ref "D1") (pin "1") (pinfunction "1_1") (pintype "passive"))
      (node (ref "EC1") (pin "2") (pinfunction "2_2") (pintype "passive"))
      (node (ref "JA1") (pin "2") (pinfunction "2_2") (pintype "passive"))
      (node (ref "M1") (pin "1") (pinfunction "1_1") (pintype "passive"))
      (node (ref "M2") (pin "1") (pinfunction "1_1") (pintype "passive"))
      (node (ref "M3") (pin "1") (pinfunction "1_1") (pintype "passive"))
      (node (ref "M4") (pin "1") (pinfunction "1_1") (pintype "passive"))
      (node (ref "R10") (pin "2") (pinfunction "2_2") (pintype "passive"))
      (node (ref "R11") (pin "2") (pinfunction "2_2") (pintype "passive"))
      (node (ref "R12") (pin "2") (pinfunction "2_2") (pintype "passive"))
      (node (ref "R19") (pin "2") (pinfunction "2_2") (pintype "passive"))
      (node (ref "R3") (pin "2") (pinfunction "2_2") (pintype "passive"))
      (node (ref "R5") (pin "2") (pinfunction "2_2") (pintype "passive"))
      (node (ref "R6") (pin "2") (pinfunction "2_2") (pintype "passive"))
      (node (ref "R9") (pin "2") (pinfunction "2_2") (pintype "passive"))
      (node (ref "U1") (pin "20") (pinfunction "VCC12I_20") (pintype "power_in"))
      (node (ref "U1") (pin "57") (pinfunction "TESTEN_57") (pintype "passive"))
      (node (ref "U1") (pin "G") (pinfunction "G_G") (pintype "passive"))
      (node (ref "U2") (pin "1") (pinfunction "GND_1") (pintype "passive"))
      (node (ref "U3") (pin "4") (pinfunction "GND_4") (pintype "passive"))
      (node (ref "U4") (pin "1") (pinfunction "GND_1") (pintype "passive"))
      (node (ref "USB1") (pin "10") (pinfunction "GND_10") (pintype "passive"))
      (node (ref "USB1") (pin "11") (pinfunction "GND_11") (pintype "passive"))
      (node (ref "USB1") (pin "4") (pinfunction "GND_4") (pintype "passive"))
      (node (ref "USB1") (pin "7") (pinfunction "GND_7") (pintype "passive"))
      (node (ref "USB2") (pin "10") (pinfunction "GND_10") (pintype "passive"))
      (node (ref "USB2") (pin "11") (pinfunction "GND_11") (pintype "passive"))
      (node (ref "USB2") (pin "4") (pinfunction "GND_4") (pintype "passive"))
      (node (ref "USB2") (pin "7") (pinfunction "GND_7") (pintype "passive"))
      (node (ref "USB3") (pin "10") (pinfunction "GND_10") (pintype "passive"))
      (node (ref "USB3") (pin "11") (pinfunction "GND_11") (pintype "passive"))
      (node (ref "USB3") (pin "4") (pinfunction "GND_4") (pintype "passive"))
      (node (ref "USB3") (pin "7") (pinfunction "GND_7") (pintype "passive"))
      (node (ref "USB4") (pin "10") (pinfunction "GND_10") (pintype "passive"))
      (node (ref "USB4") (pin "11") (pinfunction "GND_11") (pintype "passive"))
      (node (ref "USB4") (pin "4") (pinfunction "GND_4") (pintype "passive"))
      (node (ref "USB4") (pin "7") (pinfunction "GND_7") (pintype "passive"))
      (node (ref "USB5") (pin "10") (pinfunction "GND_10") (pintype "passive"))
      (node (ref "USB5") (pin "11") (pinfunction "GND_11") (pintype "passive"))
      (node (ref "USB5") (pin "4") (pinfunction "GND_4") (pintype "passive"))
      (node (ref "USB5") (pin "7") (pinfunction "GND_7") (pintype "passive"))
      (node (ref "Y1") (pin "3") (pinfunction "3_3") (pintype "passive"))
      (node (ref "Y1") (pin "4") (pinfunction "4_4") (pintype "passive"))
    )
    (net (code "66") (name "Net-(LED1-K)") (class "Default")
      (node (ref "LED1") (pin "2") (pinfunction "K_2") (pintype "passive"))
      (node (ref "R9") (pin "1") (pinfunction "1_1") (pintype "passive"))
    )
    (net (code "67") (name "Net-(LED2-K)") (class "Default")
      (node (ref "LED2") (pin "2") (pinfunction "K_2") (pintype "passive"))
      (node (ref "R10") (pin "1") (pinfunction "1_1") (pintype "passive"))
    )
    (net (code "68") (name "Net-(LED3-K)") (class "Default")
      (node (ref "LED3") (pin "2") (pinfunction "K_2") (pintype "passive"))
      (node (ref "R11") (pin "1") (pinfunction "1_1") (pintype "passive"))
    )
    (net (code "69") (name "Net-(LED4-K)") (class "Default")
      (node (ref "LED4") (pin "2") (pinfunction "K_2") (pintype "passive"))
      (node (ref "R12") (pin "1") (pinfunction "1_1") (pintype "passive"))
    )
    (net (code "70") (name "Net-(Q1-G)") (class "Default")
      (node (ref "Q1") (pin "1") (pinfunction "G_1") (pintype "passive"))
      (node (ref "R16") (pin "2") (pinfunction "2_2") (pintype "passive"))
    )
    (net (code "71") (name "Net-(U1-LX)") (class "Default")
      (node (ref "L1") (pin "1") (pinfunction "1_1") (pintype "passive"))
      (node (ref "U1") (pin "39") (pinfunction "LX_39") (pintype "passive"))
    )
    (net (code "72") (name "Net-(U1-NC)") (class "Default")
      (node (ref "R1") (pin "2") (pinfunction "2_2") (pintype "passive"))
      (node (ref "U1") (pin "40") (pinfunction "NC_40") (pintype "power_in"))
    )
    (net (code "73") (name "Net-(USB1-+5V)") (class "Default")
      (node (ref "C33") (pin "1") (pinfunction "1_1") (pintype "passive"))
      (node (ref "LB1") (pin "2") (pinfunction "2_2") (pintype "passive"))
      (node (ref "USB1") (pin "1") (pinfunction "+5V_1") (pintype "passive"))
    )
    (net (code "74") (name "Net-(USB2-+5V)") (class "Default")
      (node (ref "C35") (pin "1") (pinfunction "1_1") (pintype "passive"))
      (node (ref "C36") (pin "1") (pinfunction "1_1") (pintype "passive"))
      (node (ref "C37") (pin "1") (pinfunction "1_1") (pintype "passive"))
      (node (ref "LB2") (pin "2") (pinfunction "2_2") (pintype "passive"))
      (node (ref "USB2") (pin "1") (pinfunction "+5V_1") (pintype "passive"))
    )
    (net (code "75") (name "Net-(USB3-+5V)") (class "Default")
      (node (ref "C41") (pin "1") (pinfunction "1_1") (pintype "passive"))
      (node (ref "C42") (pin "1") (pinfunction "1_1") (pintype "passive"))
      (node (ref "C43") (pin "1") (pinfunction "1_1") (pintype "passive"))
      (node (ref "LB3") (pin "2") (pinfunction "2_2") (pintype "passive"))
      (node (ref "USB3") (pin "1") (pinfunction "+5V_1") (pintype "passive"))
    )
    (net (code "76") (name "Net-(USB4-+5V)") (class "Default")
      (node (ref "C47") (pin "1") (pinfunction "1_1") (pintype "passive"))
      (node (ref "C48") (pin "1") (pinfunction "1_1") (pintype "passive"))
      (node (ref "C49") (pin "1") (pinfunction "1_1") (pintype "passive"))
      (node (ref "LB4") (pin "2") (pinfunction "2_2") (pintype "passive"))
      (node (ref "USB4") (pin "1") (pinfunction "+5V_1") (pintype "passive"))
    )
    (net (code "77") (name "Net-(USB5-+5V)") (class "Default")
      (node (ref "C53") (pin "1") (pinfunction "1_1") (pintype "passive"))
      (node (ref "C54") (pin "1") (pinfunction "1_1") (pintype "passive"))
      (node (ref "C55") (pin "1") (pinfunction "1_1") (pintype "passive"))
      (node (ref "LB5") (pin "2") (pinfunction "2_2") (pintype "passive"))
      (node (ref "USB5") (pin "1") (pinfunction "+5V_1") (pintype "passive"))
    )
    (net (code "78") (name "VBUS") (class "Default")
      (node (ref "C32") (pin "1") (pinfunction "1_1") (pintype "passive"))
      (node (ref "LB1") (pin "1") (pinfunction "1_1") (pintype "passive"))
      (node (ref "Q1") (pin "3") (pinfunction "D_3") (pintype "passive"))
      (node (ref "R4") (pin "1") (pinfunction "1_1") (pintype "passive"))
    )
    (net (code "79") (name "VCC5V") (class "Default")
      (node (ref "C2") (pin "1") (pinfunction "1_1") (pintype "passive"))
      (node (ref "C26") (pin "2") (pinfunction "2_2") (pintype "passive"))
      (node (ref "C27") (pin "2") (pinfunction "2_2") (pintype "passive"))
      (node (ref "C28") (pin "2") (pinfunction "2_2") (pintype "passive"))
      (node (ref "C3") (pin "1") (pinfunction "1_1") (pintype "passive"))
      (node (ref "D1") (pin "2") (pinfunction "2_2") (pintype "passive"))
      (node (ref "EC1") (pin "1") (pinfunction "1_1") (pintype "passive"))
      (node (ref "FU1") (pin "2") (pinfunction "2_2") (pintype "passive"))
      (node (ref "JA1") (pin "1") (pinfunction "1_1") (pintype "passive"))
      (node (ref "Q1") (pin "2") (pinfunction "S_2") (pintype "passive"))
      (node (ref "R14") (pin "1") (pinfunction "1_1") (pintype "passive"))
      (node (ref "U1") (pin "19") (pinfunction "VCC5I_19") (pintype "power_in"))
      (node (ref "U1") (pin "38") (pinfunction "VCC5I_38") (pintype "passive"))
      (node (ref "U4") (pin "2") (pinfunction "VIN_2") (pintype "passive"))
      (node (ref "U4") (pin "3") (pinfunction "VIN_3") (pintype "passive"))
    )
    (net (code "80") (name "VDP1~3") (class "Default")
      (node (ref "C34") (pin "1") (pinfunction "1_1") (pintype "passive"))
      (node (ref "C40") (pin "1") (pinfunction "1_1") (pintype "passive"))
      (node (ref "C46") (pin "1") (pinfunction "1_1") (pintype "passive"))
      (node (ref "FU1") (pin "1") (pinfunction "1_1") (pintype "passive"))
      (node (ref "LB2") (pin "1") (pinfunction "1_1") (pintype "passive"))
      (node (ref "LB3") (pin "1") (pinfunction "1_1") (pintype "passive"))
      (node (ref "LB4") (pin "1") (pinfunction "1_1") (pintype "passive"))
      (node (ref "R18") (pin "1") (pinfunction "1_1") (pintype "passive"))
    )
    (net (code "81") (name "VDP4") (class "Default")
      (node (ref "C25") (pin "1") (pinfunction "1_1") (pintype "passive"))
      (node (ref "C52") (pin "1") (pinfunction "1_1") (pintype "passive"))
      (node (ref "LB5") (pin "1") (pinfunction "1_1") (pintype "passive"))
      (node (ref "U4") (pin "6") (pinfunction "OUT_6") (pintype "passive"))
      (node (ref "U4") (pin "7") (pinfunction "OUT_7") (pintype "passive"))
      (node (ref "U4") (pin "8") (pinfunction "OUT_8") (pintype "passive"))
    )
    (net (code "82") (name "unconnected-(U1-DC10FB-Pad21)") (class "Default")
      (node (ref "U1") (pin "21") (pinfunction "DC10FB_21") (pintype "passive+no_connect"))
    )
  )
)
